# I2Sspeaker.net
KiCad netlist of a schematic drawn in EAGLE
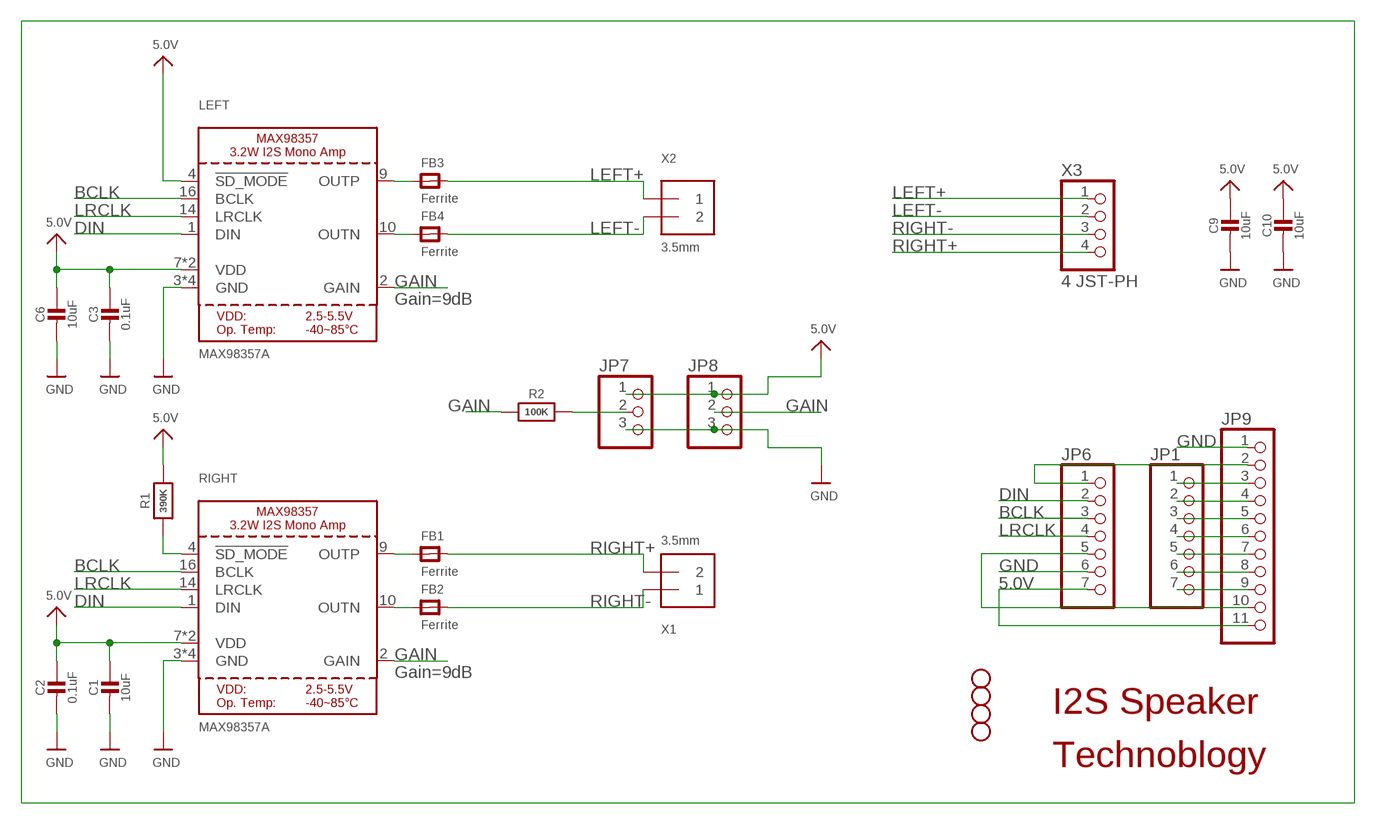
[diagram p0: schematic, sheet 1]

(export (version "E")
  (design (tool "Eeschema 10.0.6"))
  (components
    (comp (ref "C1")
      (value "10uF")
      (footprint "eagle-import:0805-NO")
      (libsource (lib "eagle-import") (part "CAP_CERAMIC0805-NOOUTLINE"))
    )
    (comp (ref "C2")
      (value "0.1uF")
      (footprint "eagle-import:0805-NO")
      (libsource (lib "eagle-import") (part "CAP_CERAMIC0805-NOOUTLINE"))
    )
    (comp (ref "C3")
      (value "0.1uF")
      (footprint "eagle-import:0805-NO")
      (libsource (lib "eagle-import") (part "CAP_CERAMIC0805-NOOUTLINE"))
    )
    (comp (ref "C6")
      (value "10uF")
      (footprint "eagle-import:0805-NO")
      (libsource (lib "eagle-import") (part "CAP_CERAMIC0805-NOOUTLINE"))
    )
    (comp (ref "C9")
      (value "10uF")
      (footprint "eagle-import:0805-NO")
      (libsource (lib "eagle-import") (part "CAP_CERAMIC0805-NOOUTLINE"))
    )
    (comp (ref "C10")
      (value "10uF")
      (footprint "eagle-import:0805-NO")
      (libsource (lib "eagle-import") (part "CAP_CERAMIC0805-NOOUTLINE"))
    )
    (comp (ref "FB1")
      (value "Ferrite")
      (footprint "eagle-import:0805-NO")
      (libsource (lib "eagle-import") (part "FERRITE-0805NO"))
    )
    (comp (ref "FB2")
      (value "Ferrite")
      (footprint "eagle-import:0805-NO")
      (libsource (lib "eagle-import") (part "FERRITE-0805NO"))
    )
    (comp (ref "FB3")
      (value "Ferrite")
      (footprint "eagle-import:0805-NO")
      (libsource (lib "eagle-import") (part "FERRITE-0805NO"))
    )
    (comp (ref "FB4")
      (value "Ferrite")
      (footprint "eagle-import:0805-NO")
      (libsource (lib "eagle-import") (part "FERRITE-0805NO"))
    )
    (comp (ref "JP1")
      (value "HEADER-1X7ROUND")
      (footprint "eagle-import:1X07_ROUND")
      (libsource (lib "eagle-import") (part "HEADER-1X7ROUND"))
    )
    (comp (ref "JP2")
      (value "STAND-OFF")
      (footprint "eagle-import:STAND-OFF")
      (libsource (lib "eagle-import") (part "STAND-OFF"))
    )
    (comp (ref "JP3")
      (value "STAND-OFF")
      (footprint "eagle-import:STAND-OFF")
      (libsource (lib "eagle-import") (part "STAND-OFF"))
    )
    (comp (ref "JP4")
      (value "STAND-OFF")
      (footprint "eagle-import:STAND-OFF")
      (libsource (lib "eagle-import") (part "STAND-OFF"))
    )
    (comp (ref "JP5")
      (value "STAND-OFF")
      (footprint "eagle-import:STAND-OFF")
      (libsource (lib "eagle-import") (part "STAND-OFF"))
    )
    (comp (ref "JP6")
      (value "HEADER-1X7ROUND")
      (footprint "eagle-import:1X07_ROUND")
      (libsource (lib "eagle-import") (part "HEADER-1X7ROUND"))
    )
    (comp (ref "JP7")
      (value "HEADER-1X3ROUND")
      (footprint "eagle-import:1X03_ROUND")
      (libsource (lib "eagle-import") (part "HEADER-1X3ROUND"))
    )
    (comp (ref "JP8")
      (value "HEADER-1X3ROUND")
      (footprint "eagle-import:1X03_ROUND")
      (libsource (lib "eagle-import") (part "HEADER-1X3ROUND"))
    )
    (comp (ref "JP9")
      (value "HEADER-1X11")
      (footprint "eagle-import:1X11_ROUND")
      (libsource (lib "eagle-import") (part "HEADER-1X11"))
    )
    (comp (ref "LEFT")
      (value "MAX98357A")
      (footprint "eagle-import:QFN16_3MM")
      (libsource (lib "eagle-import") (part "AUDIOAMP_MAX98357"))
    )
    (comp (ref "R1")
      (value "390K")
      (footprint "eagle-import:0805-NO")
      (libsource (lib "eagle-import") (part "RESISTOR0805_NOOUTLINE"))
    )
    (comp (ref "R2")
      (value "100K")
      (footprint "eagle-import:0805-NO")
      (libsource (lib "eagle-import") (part "RESISTOR0805_NOOUTLINE"))
    )
    (comp (ref "RIGHT")
      (value "MAX98357A")
      (footprint "eagle-import:QFN16_3MM")
      (libsource (lib "eagle-import") (part "AUDIOAMP_MAX98357"))
    )
    (comp (ref "X1")
      (value "3.5mm")
      (footprint "eagle-import:TERMBLOCK_1X2-3.5MM")
      (libsource (lib "eagle-import") (part "TERMBLOCK_1X2"))
    )
    (comp (ref "X2")
      (value "3.5mm")
      (footprint "eagle-import:TERMBLOCK_1X2-3.5MM")
      (libsource (lib "eagle-import") (part "TERMBLOCK_1X2"))
    )
    (comp (ref "X3")
      (value "4 JST-PH")
      (footprint "eagle-import:JSTPH4")
      (libsource (lib "eagle-import") (part "CON_JST_PH_4PIN"))
    )
  )
  (nets
    (net (code "1") (name "/BCLK") (class "Default")
      (node (ref "JP6") (pin "3") (pinfunction "3_3") (pintype "passive"))
      (node (ref "LEFT") (pin "16") (pinfunction "BCLK_16") (pintype "bidirectional"))
      (node (ref "RIGHT") (pin "16") (pinfunction "BCLK_16") (pintype "bidirectional"))
    )
    (net (code "2") (name "/DIN") (class "Default")
      (node (ref "JP6") (pin "2") (pinfunction "2_2") (pintype "passive"))
      (node (ref "LEFT") (pin "1") (pinfunction "DIN_1") (pintype "bidirectional"))
      (node (ref "RIGHT") (pin "1") (pinfunction "DIN_1") (pintype "bidirectional"))
    )
    (net (code "3") (name "/GAIN") (class "Default")
      (node (ref "JP8") (pin "2") (pinfunction "2_2") (pintype "passive"))
      (node (ref "LEFT") (pin "2") (pinfunction "GAIN_2") (pintype "bidirectional"))
      (node (ref "R2") (pin "1") (pinfunction "1_1") (pintype "passive"))
      (node (ref "RIGHT") (pin "2") (pinfunction "GAIN_2") (pintype "bidirectional"))
    )
    (net (code "4") (name "/LEFT+") (class "Default")
      (node (ref "FB3") (pin "2") (pinfunction "P$2_2") (pintype "passive"))
      (node (ref "X2") (pin "1") (pinfunction "1_1") (pintype "passive"))
      (node (ref "X3") (pin "1") (pinfunction "1_1") (pintype "passive"))
    )
    (net (code "5") (name "/LEFT-") (class "Default")
      (node (ref "FB4") (pin "2") (pinfunction "P$2_2") (pintype "passive"))
      (node (ref "X2") (pin "2") (pinfunction "2_2") (pintype "passive"))
      (node (ref "X3") (pin "2") (pinfunction "2_2") (pintype "passive"))
    )
    (net (code "6") (name "/LRCLK") (class "Default")
      (node (ref "JP6") (pin "4") (pinfunction "4_4") (pintype "passive"))
      (node (ref "LEFT") (pin "14") (pinfunction "LRCLK_14") (pintype "bidirectional"))
      (node (ref "RIGHT") (pin "14") (pinfunction "LRCLK_14") (pintype "bidirectional"))
    )
    (net (code "7") (name "/RIGHT+") (class "Default")
      (node (ref "FB1") (pin "2") (pinfunction "P$2_2") (pintype "passive"))
      (node (ref "X1") (pin "2") (pinfunction "2_2") (pintype "passive"))
      (node (ref "X3") (pin "4") (pinfunction "4_4") (pintype "passive"))
    )
    (net (code "8") (name "/RIGHT-") (class "Default")
      (node (ref "FB2") (pin "2") (pinfunction "P$2_2") (pintype "passive"))
      (node (ref "X1") (pin "1") (pinfunction "1_1") (pintype "passive"))
      (node (ref "X3") (pin "3") (pinfunction "3_3") (pintype "passive"))
    )
    (net (code "9") (name "5.0V") (class "Default")
      (node (ref "C1") (pin "1") (pinfunction "1_1") (pintype "passive"))
      (node (ref "C10") (pin "1") (pinfunction "1_1") (pintype "passive"))
      (node (ref "C2") (pin "1") (pinfunction "1_1") (pintype "passive"))
      (node (ref "C3") (pin "1") (pinfunction "1_1") (pintype "passive"))
      (node (ref "C6") (pin "1") (pinfunction "1_1") (pintype "passive"))
      (node (ref "C9") (pin "1") (pinfunction "1_1") (pintype "passive"))
      (node (ref "JP6") (pin "7") (pinfunction "7_7") (pintype "passive"))
      (node (ref "JP7") (pin "1") (pinfunction "1_1") (pintype "passive"))
      (node (ref "JP8") (pin "1") (pinfunction "1_1") (pintype "passive"))
      (node (ref "JP9") (pin "11") (pinfunction "11_11") (pintype "passive"))
      (node (ref "LEFT") (pin "4") (pinfunction "~{SD_MODE}_4") (pintype "bidirectional"))
      (node (ref "LEFT") (pin "7") (pinfunction "VDD_7") (pintype "power_in"))
      (node (ref "LEFT") (pin "8") (pinfunction "VDD_8") (pintype "power_in"))
      (node (ref "R1") (pin "2") (pinfunction "2_2") (pintype "passive"))
      (node (ref "RIGHT") (pin "7") (pinfunction "VDD_7") (pintype "power_in"))
      (node (ref "RIGHT") (pin "8") (pinfunction "VDD_8") (pintype "power_in"))
    )
    (net (code "10") (name "GND") (class "Default")
      (node (ref "C1") (pin "2") (pinfunction "2_2") (pintype "passive"))
      (node (ref "C10") (pin "2") (pinfunction "2_2") (pintype "passive"))
      (node (ref "C2") (pin "2") (pinfunction "2_2") (pintype "passive"))
      (node (ref "C3") (pin "2") (pinfunction "2_2") (pintype "passive"))
      (node (ref "C6") (pin "2") (pinfunction "2_2") (pintype "passive"))
      (node (ref "C9") (pin "2") (pinfunction "2_2") (pintype "passive"))
      (node (ref "JP6") (pin "6") (pinfunction "6_6") (pintype "passive"))
      (node (ref "JP7") (pin "3") (pinfunction "3_3") (pintype "passive"))
      (node (ref "JP8") (pin "3") (pinfunction "3_3") (pintype "passive"))
      (node (ref "JP9") (pin "1") (pinfunction "1_1") (pintype "passive"))
      (node (ref "LEFT") (pin "11") (pinfunction "GND_11") (pintype "power_in"))
      (node (ref "LEFT") (pin "15") (pinfunction "GND_15") (pintype "power_in"))
      (node (ref "LEFT") (pin "3") (pinfunction "GND_3") (pintype "power_in"))
      (node (ref "LEFT") (pin "THERMAL") (pinfunction "GND_THERMAL") (pintype "power_in"))
      (node (ref "RIGHT") (pin "11") (pinfunction "GND_11") (pintype "power_in"))
      (node (ref "RIGHT") (pin "15") (pinfunction "GND_15") (pintype "power_in"))
      (node (ref "RIGHT") (pin "3") (pinfunction "GND_3") (pintype "power_in"))
      (node (ref "RIGHT") (pin "THERMAL") (pinfunction "GND_THERMAL") (pintype "power_in"))
    )
    (net (code "11") (name "Net-(FB1-P$1)") (class "Default")
      (node (ref "FB1") (pin "1") (pinfunction "P$1_1") (pintype "passive"))
      (node (ref "RIGHT") (pin "9") (pinfunction "OUTP_9") (pintype "output"))
    )
    (net (code "12") (name "Net-(FB2-P$1)") (class "Default")
      (node (ref "FB2") (pin "1") (pinfunction "P$1_1") (pintype "passive"))
      (node (ref "RIGHT") (pin "10") (pinfunction "OUTN_10") (pintype "output"))
    )
    (net (code "13") (name "Net-(FB3-P$1)") (class "Default")
      (node (ref "FB3") (pin "1") (pinfunction "P$1_1") (pintype "passive"))
      (node (ref "LEFT") (pin "9") (pinfunction "OUTP_9") (pintype "output"))
    )
    (net (code "14") (name "Net-(FB4-P$1)") (class "Default")
      (node (ref "FB4") (pin "1") (pinfunction "P$1_1") (pintype "passive"))
      (node (ref "LEFT") (pin "10") (pinfunction "OUTN_10") (pintype "output"))
    )
    (net (code "15") (name "Net-(JP1-Pad1)") (class "Default")
      (node (ref "JP1") (pin "1") (pinfunction "1_1") (pintype "passive"))
      (node (ref "JP9") (pin "3") (pinfunction "3_3") (pintype "passive"))
    )
    (net (code "16") (name "Net-(JP1-Pad2)") (class "Default")
      (node (ref "JP1") (pin "2") (pinfunction "2_2") (pintype "passive"))
      (node (ref "JP9") (pin "4") (pinfunction "4_4") (pintype "passive"))
    )
    (net (code "17") (name "Net-(JP1-Pad3)") (class "Default")
      (node (ref "JP1") (pin "3") (pinfunction "3_3") (pintype "passive"))
      (node (ref "JP9") (pin "5") (pinfunction "5_5") (pintype "passive"))
    )
    (net (code "18") (name "Net-(JP1-Pad4)") (class "Default")
      (node (ref "JP1") (pin "4") (pinfunction "4_4") (pintype "passive"))
      (node (ref "JP9") (pin "6") (pinfunction "6_6") (pintype "passive"))
    )
    (net (code "19") (name "Net-(JP1-Pad5)") (class "Default")
      (node (ref "JP1") (pin "5") (pinfunction "5_5") (pintype "passive"))
      (node (ref "JP9") (pin "7") (pinfunction "7_7") (pintype "passive"))
    )
    (net (code "20") (name "Net-(JP1-Pad6)") (class "Default")
      (node (ref "JP1") (pin "6") (pinfunction "6_6") (pintype "passive"))
      (node (ref "JP9") (pin "8") (pinfunction "8_8") (pintype "passive"))
    )
    (net (code "21") (name "Net-(JP1-Pad7)") (class "Default")
      (node (ref "JP1") (pin "7") (pinfunction "7_7") (pintype "passive"))
      (node (ref "JP9") (pin "9") (pinfunction "9_9") (pintype "passive"))
    )
    (net (code "22") (name "Net-(JP6-Pad1)") (class "Default")
      (node (ref "JP6") (pin "1") (pinfunction "1_1") (pintype "passive"))
      (node (ref "JP9") (pin "2") (pinfunction "2_2") (pintype "passive"))
    )
    (net (code "23") (name "Net-(JP6-Pad5)") (class "Default")
      (node (ref "JP6") (pin "5") (pinfunction "5_5") (pintype "passive"))
      (node (ref "JP9") (pin "10") (pinfunction "10_10") (pintype "passive"))
    )
    (net (code "24") (name "Net-(JP7-Pad2)") (class "Default")
      (node (ref "JP7") (pin "2") (pinfunction "2_2") (pintype "passive"))
      (node (ref "R2") (pin "2") (pinfunction "2_2") (pintype "passive"))
    )
    (net (code "25") (name "Net-(RIGHT-~{SD_MODE})") (class "Default")
      (node (ref "R1") (pin "1") (pinfunction "1_1") (pintype "passive"))
      (node (ref "RIGHT") (pin "4") (pinfunction "~{SD_MODE}_4") (pintype "bidirectional"))
    )
  )
)
